# DXP.net
KiCad netlist of a schematic drawn in Altium Designer
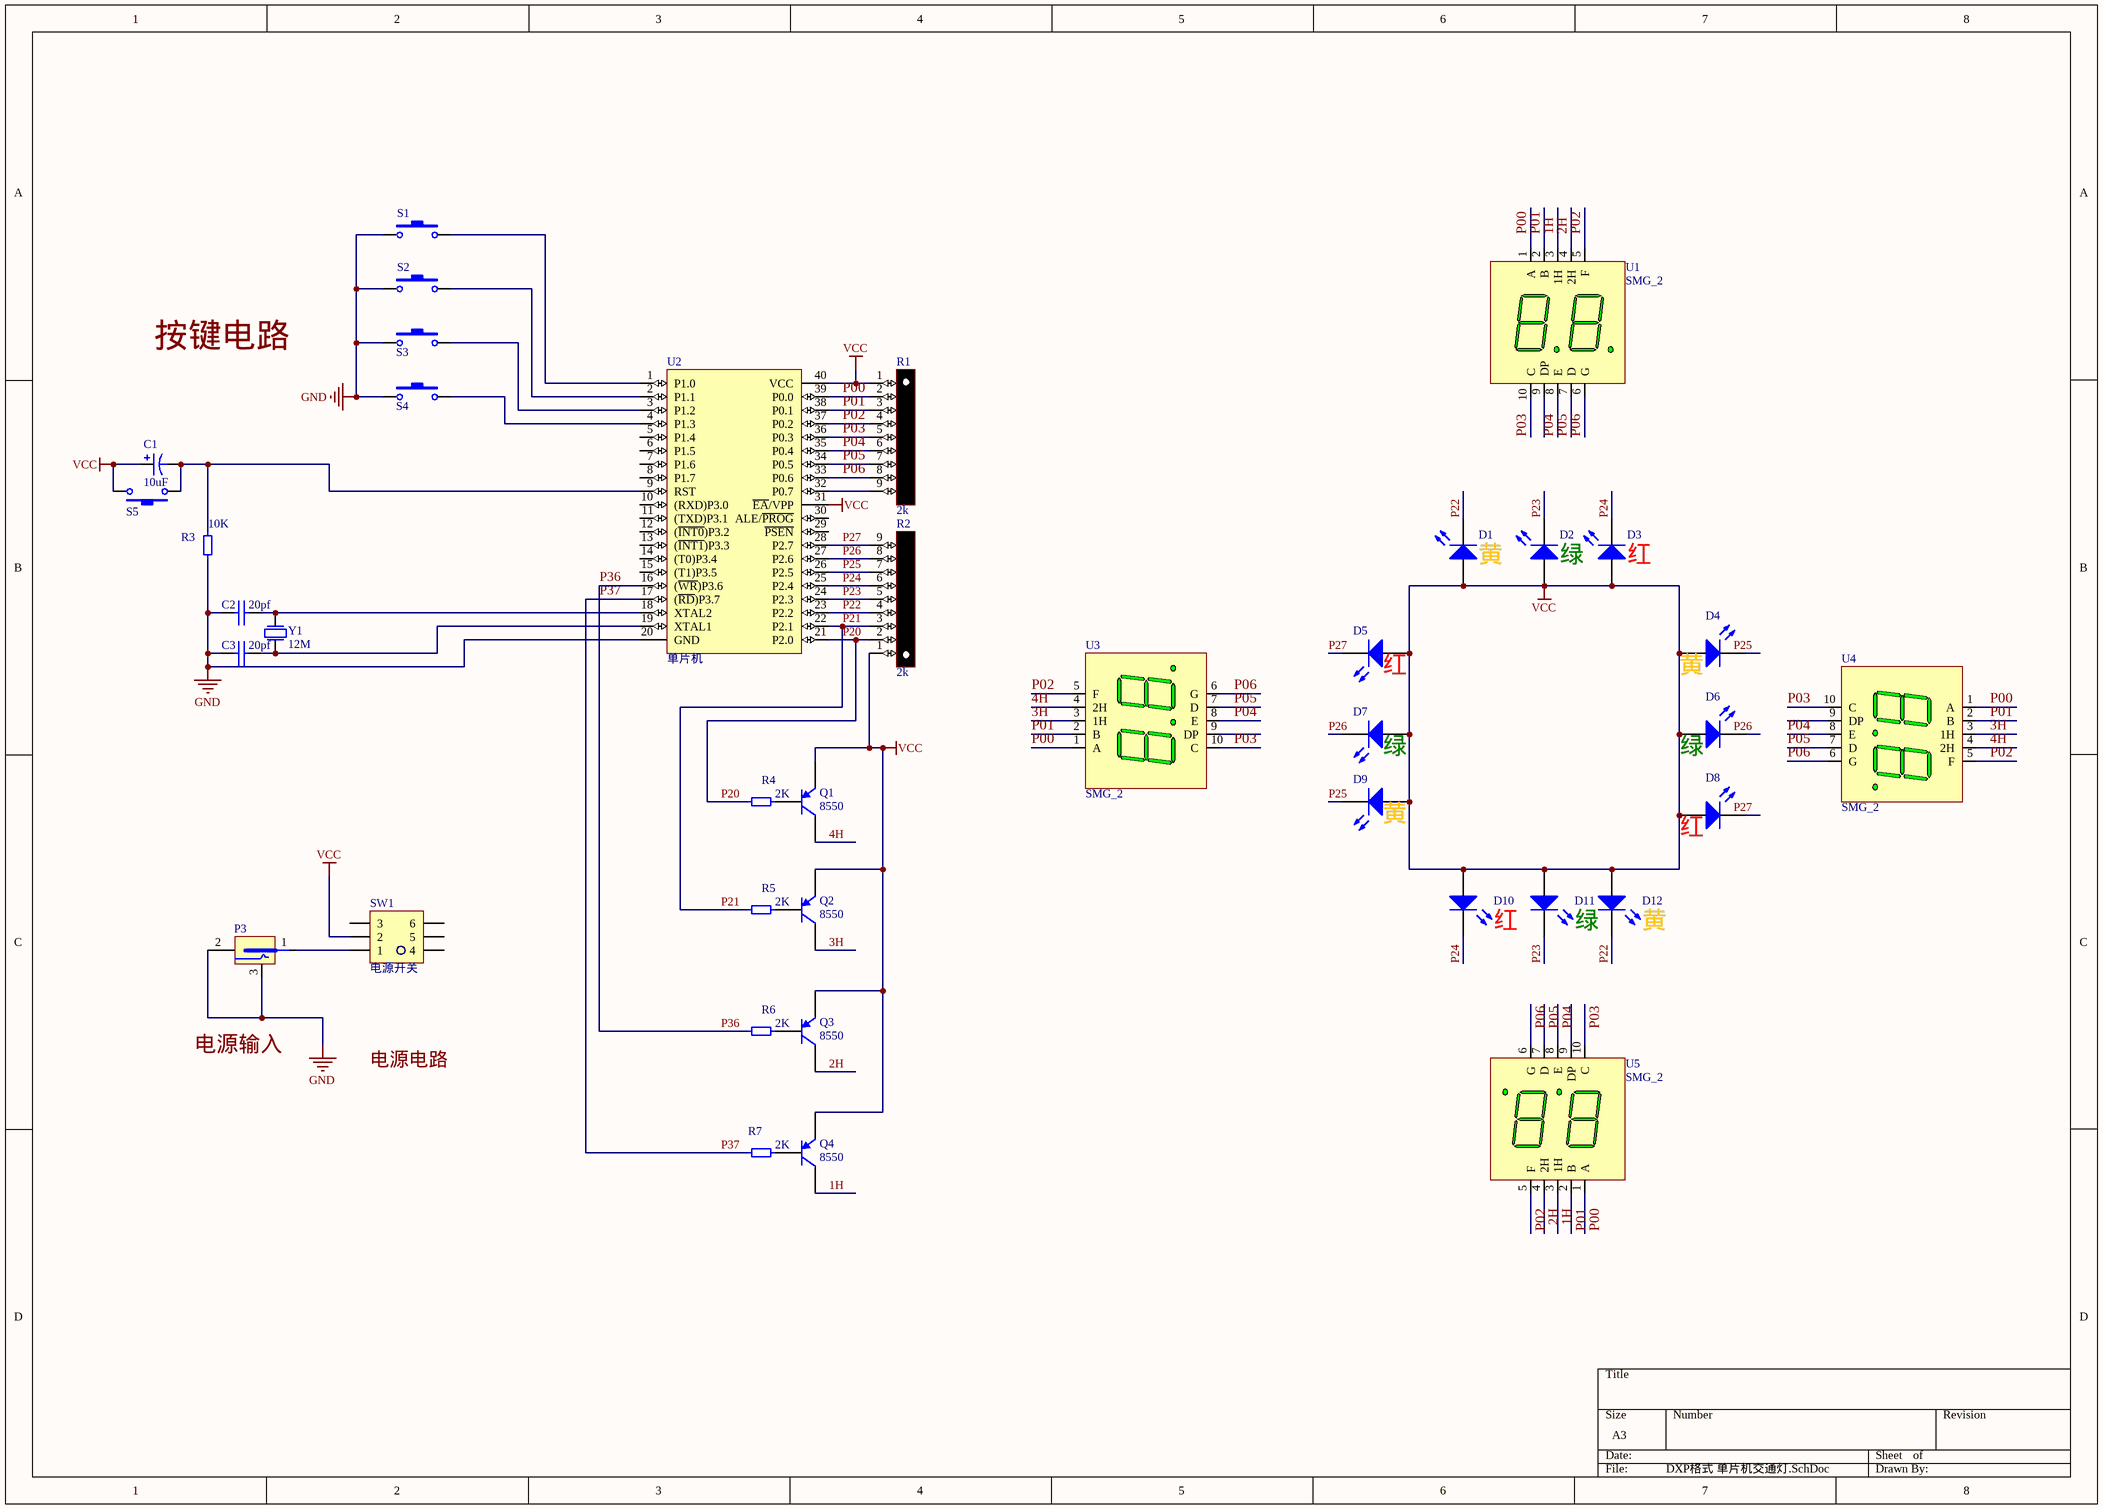
[diagram p0: DXP格式 单片机交通灯.SchDoc]

(export (version "E")
  (design (tool "Eeschema 10.0.6"))
  (components
    (comp (ref "C1")
      (value "10uF")
      (footprint "C_10")
      (description "Polarized Capacitor (Radial)")
      (fields (field (name "PUBLISHER") "Altium Limited"))
      (libsource (lib "简易动环监控系统") (part "Cap Pol1"))
    )
    (comp (ref "C2")
      (value "20pf")
      (footprint "CAP CP")
      (description "电容")
      (libsource (lib "C8051F020最小2") (part "CAP"))
    )
    (comp (ref "C3")
      (value "20pf")
      (footprint "CAP CP")
      (description "电容")
      (libsource (lib "C8051F020最小2") (part "CAP"))
    )
    (comp (ref "D1") (value "黄") (footprint "LED2J") (description "发光二极管") (libsource (lib "亮") (part "LED")))
    (comp (ref "D2") (value "绿") (footprint "LED2J") (description "发光二极管") (libsource (lib "亮") (part "LED")))
    (comp (ref "D3") (value "红") (footprint "LED2J") (description "发光二极管") (libsource (lib "亮") (part "LED")))
    (comp (ref "D4") (value "黄") (footprint "LED2J") (description "发光二极管") (libsource (lib "亮") (part "LED")))
    (comp (ref "D5") (value "红") (footprint "LED2J") (description "发光二极管") (libsource (lib "亮") (part "LED")))
    (comp (ref "D6") (value "绿") (footprint "LED2J") (description "发光二极管") (libsource (lib "亮") (part "LED")))
    (comp (ref "D7") (value "绿") (footprint "LED2J") (description "发光二极管") (libsource (lib "亮") (part "LED")))
    (comp (ref "D8") (value "红") (footprint "LED2J") (description "发光二极管") (libsource (lib "亮") (part "LED")))
    (comp (ref "D9") (value "黄") (footprint "LED2J") (description "发光二极管") (libsource (lib "亮") (part "LED")))
    (comp (ref "D10")
      (value "红")
      (footprint "LED2J")
      (description "发光二极管")
      (libsource (lib "亮") (part "LED"))
    )
    (comp (ref "D11")
      (value "绿")
      (footprint "LED2J")
      (description "发光二极管")
      (libsource (lib "亮") (part "LED"))
    )
    (comp (ref "D12")
      (value "黄")
      (footprint "LED2J")
      (description "发光二极管")
      (libsource (lib "亮") (part "LED"))
    )
    (comp (ref "P3") (value "电源输入") (footprint "DC2.1") (libsource (lib "我自己的") (part "POWER")))
    (comp (ref "Q1")
      (value "8550")
      (footprint "s三极管直插")
      (description "PNP General Purpose Amplifier")
      (fields (field (name "PUBLISHER") "Altium Limited"))
      (libsource (lib "Miscellaneous Devices") (part "2N3906"))
    )
    (comp (ref "Q2")
      (value "8550")
      (footprint "s三极管直插")
      (description "PNP General Purpose Amplifier")
      (fields (field (name "PUBLISHER") "Altium Limited"))
      (libsource (lib "Miscellaneous Devices") (part "2N3906"))
    )
    (comp (ref "Q3")
      (value "8550")
      (footprint "s三极管直插")
      (description "PNP General Purpose Amplifier")
      (fields (field (name "PUBLISHER") "Altium Limited"))
      (libsource (lib "Miscellaneous Devices") (part "2N3906"))
    )
    (comp (ref "Q4")
      (value "8550")
      (footprint "s三极管直插")
      (description "PNP General Purpose Amplifier")
      (fields (field (name "PUBLISHER") "Altium Limited"))
      (libsource (lib "Miscellaneous Devices") (part "2N3906"))
    )
    (comp (ref "R1") (value "2k") (footprint "SIP9") (description "排阻") (libsource (lib "亮") (part "RES9")))
    (comp (ref "R2") (value "2k") (footprint "SIP9") (description "排阻") (libsource (lib "") (part "RES9_1")))
    (comp (ref "R3") (value "10K") (footprint "AXIAL0.3") (libsource (lib "C8051F020最小2") (part "RES2")))
    (comp (ref "R4") (value "2K") (footprint "AXIAL0.3") (libsource (lib "C8051F020最小2") (part "RES2")))
    (comp (ref "R5") (value "2K") (footprint "AXIAL0.3") (libsource (lib "C8051F020最小2") (part "RES2")))
    (comp (ref "R6") (value "2K") (footprint "AXIAL0.3") (libsource (lib "C8051F020最小2") (part "RES2")))
    (comp (ref "R7") (value "2K") (footprint "AXIAL0.3") (libsource (lib "C8051F020最小2") (part "RES2")))
    (comp (ref "S1")
      (value "SW-PB")
      (footprint "key")
      (description "Switch")
      (fields (field (name "PUBLISHER") "Altium Limited"))
      (libsource (lib "实验板原理图") (part "SW-PB"))
    )
    (comp (ref "S2")
      (value "SW-PB")
      (footprint "key")
      (description "Switch")
      (fields (field (name "PUBLISHER") "Altium Limited"))
      (libsource (lib "实验板原理图") (part "SW-PB"))
    )
    (comp (ref "S3")
      (value "SW-PB")
      (footprint "key")
      (description "Switch")
      (fields (field (name "PUBLISHER") "Altium Limited"))
      (libsource (lib "实验板原理图") (part "SW-PB"))
    )
    (comp (ref "S4")
      (value "SW-PB")
      (footprint "key")
      (description "Switch")
      (fields (field (name "PUBLISHER") "Altium Limited"))
      (libsource (lib "实验板原理图") (part "SW-PB"))
    )
    (comp (ref "S5")
      (value "SW-PB")
      (footprint "key")
      (description "Switch")
      (fields (field (name "PUBLISHER") "Altium Limited"))
      (libsource (lib "实验板原理图") (part "SW-PB"))
    )
    (comp (ref "SW1") (value "电源开关") (footprint "sw_自锁 1") (libsource (lib "我自己的") (part "SW1")))
    (comp (ref "U1") (value "SMG_2") (footprint "SMG_2") (libsource (lib "交通灯+上下班高峰调整") (part "SMG_2")))
    (comp (ref "U2") (value "单片机") (footprint "DIP40 - 做板") (libsource (lib "实验板原理图") (part "U1")))
    (comp (ref "U3") (value "SMG_2") (footprint "SMG_2") (libsource (lib "") (part "SMG_2_1")))
    (comp (ref "U4") (value "SMG_2") (footprint "SMG_2") (libsource (lib "") (part "SMG_2_2")))
    (comp (ref "U5") (value "SMG_2") (footprint "SMG_2") (libsource (lib "") (part "SMG_2_3")))
    (comp (ref "Y1")
      (value "12M")
      (footprint "XTAL")
      (description "Crystal Oscillator")
      (libsource (lib "C8051F020最小2") (part "16M"))
    )
  )
  (nets
    (net (code "1") (name "/1H") (class "Default")
      (node (ref "Q4") (pin "3") (pinfunction "C_3") (pintype "passive"))
      (node (ref "U1") (pin "3") (pinfunction "1H_3") (pintype "passive"))
      (node (ref "U5") (pin "3") (pinfunction "1H_3") (pintype "passive"))
    )
    (net (code "2") (name "/2H") (class "Default")
      (node (ref "Q3") (pin "3") (pinfunction "C_3") (pintype "passive"))
      (node (ref "U1") (pin "4") (pinfunction "2H_4") (pintype "passive"))
      (node (ref "U5") (pin "4") (pinfunction "2H_4") (pintype "passive"))
    )
    (net (code "3") (name "/3H") (class "Default")
      (node (ref "Q2") (pin "3") (pinfunction "C_3") (pintype "passive"))
      (node (ref "U3") (pin "3") (pinfunction "1H_3") (pintype "passive"))
      (node (ref "U4") (pin "3") (pinfunction "1H_3") (pintype "passive"))
    )
    (net (code "4") (name "/4H") (class "Default")
      (node (ref "Q1") (pin "3") (pinfunction "C_3") (pintype "passive"))
      (node (ref "U3") (pin "4") (pinfunction "2H_4") (pintype "passive"))
      (node (ref "U4") (pin "4") (pinfunction "2H_4") (pintype "passive"))
    )
    (net (code "5") (name "/P00") (class "Default")
      (node (ref "R1") (pin "2") (pinfunction "2_2") (pintype "bidirectional"))
      (node (ref "U1") (pin "1") (pinfunction "A_1") (pintype "passive"))
      (node (ref "U2") (pin "39") (pinfunction "P0.0_39") (pintype "bidirectional"))
      (node (ref "U3") (pin "1") (pinfunction "A_1") (pintype "passive"))
      (node (ref "U4") (pin "1") (pinfunction "A_1") (pintype "passive"))
      (node (ref "U5") (pin "1") (pinfunction "A_1") (pintype "passive"))
    )
    (net (code "6") (name "/P01") (class "Default")
      (node (ref "R1") (pin "3") (pinfunction "3_3") (pintype "bidirectional"))
      (node (ref "U1") (pin "2") (pinfunction "B_2") (pintype "passive"))
      (node (ref "U2") (pin "38") (pinfunction "P0.1_38") (pintype "bidirectional"))
      (node (ref "U3") (pin "2") (pinfunction "B_2") (pintype "passive"))
      (node (ref "U4") (pin "2") (pinfunction "B_2") (pintype "passive"))
      (node (ref "U5") (pin "2") (pinfunction "B_2") (pintype "passive"))
    )
    (net (code "7") (name "/P02") (class "Default")
      (node (ref "R1") (pin "4") (pinfunction "4_4") (pintype "bidirectional"))
      (node (ref "U1") (pin "5") (pinfunction "F_5") (pintype "passive"))
      (node (ref "U2") (pin "37") (pinfunction "P0.2_37") (pintype "bidirectional"))
      (node (ref "U3") (pin "5") (pinfunction "F_5") (pintype "passive"))
      (node (ref "U4") (pin "5") (pinfunction "F_5") (pintype "passive"))
      (node (ref "U5") (pin "5") (pinfunction "F_5") (pintype "passive"))
    )
    (net (code "8") (name "/P03") (class "Default")
      (node (ref "R1") (pin "5") (pinfunction "5_5") (pintype "bidirectional"))
      (node (ref "U1") (pin "10") (pinfunction "C_10") (pintype "passive"))
      (node (ref "U2") (pin "36") (pinfunction "P0.3_36") (pintype "bidirectional"))
      (node (ref "U3") (pin "10") (pinfunction "C_10") (pintype "passive"))
      (node (ref "U4") (pin "10") (pinfunction "C_10") (pintype "passive"))
      (node (ref "U5") (pin "10") (pinfunction "C_10") (pintype "passive"))
    )
    (net (code "9") (name "/P04") (class "Default")
      (node (ref "R1") (pin "6") (pinfunction "6_6") (pintype "bidirectional"))
      (node (ref "U1") (pin "8") (pinfunction "E_8") (pintype "passive"))
      (node (ref "U2") (pin "35") (pinfunction "P0.4_35") (pintype "bidirectional"))
      (node (ref "U3") (pin "8") (pinfunction "E_8") (pintype "passive"))
      (node (ref "U4") (pin "8") (pinfunction "E_8") (pintype "passive"))
      (node (ref "U5") (pin "8") (pinfunction "E_8") (pintype "passive"))
    )
    (net (code "10") (name "/P05") (class "Default")
      (node (ref "R1") (pin "7") (pinfunction "7_7") (pintype "bidirectional"))
      (node (ref "U1") (pin "7") (pinfunction "D_7") (pintype "passive"))
      (node (ref "U2") (pin "34") (pinfunction "P0.5_34") (pintype "bidirectional"))
      (node (ref "U3") (pin "7") (pinfunction "D_7") (pintype "passive"))
      (node (ref "U4") (pin "7") (pinfunction "D_7") (pintype "passive"))
      (node (ref "U5") (pin "7") (pinfunction "D_7") (pintype "passive"))
    )
    (net (code "11") (name "/P06") (class "Default")
      (node (ref "R1") (pin "8") (pinfunction "8_8") (pintype "bidirectional"))
      (node (ref "U1") (pin "6") (pinfunction "G_6") (pintype "passive"))
      (node (ref "U2") (pin "33") (pinfunction "P0.6_33") (pintype "bidirectional"))
      (node (ref "U3") (pin "6") (pinfunction "G_6") (pintype "passive"))
      (node (ref "U4") (pin "6") (pinfunction "G_6") (pintype "passive"))
      (node (ref "U5") (pin "6") (pinfunction "G_6") (pintype "passive"))
    )
    (net (code "12") (name "/P20") (class "Default")
      (node (ref "R2") (pin "2") (pinfunction "2_2") (pintype "bidirectional"))
      (node (ref "R2") (pin "3") (pinfunction "3_3") (pintype "bidirectional"))
      (node (ref "R4") (pin "2") (pinfunction "2_2") (pintype "passive"))
      (node (ref "R5") (pin "2") (pinfunction "2_2") (pintype "passive"))
      (node (ref "U2") (pin "21") (pinfunction "P2.0_21") (pintype "bidirectional"))
      (node (ref "U2") (pin "22") (pinfunction "P2.1_22") (pintype "bidirectional"))
    )
    (net (code "13") (name "/P22") (class "Default")
      (node (ref "D1") (pin "2") (pinfunction "K_2") (pintype "passive"))
      (node (ref "D12") (pin "2") (pinfunction "K_2") (pintype "passive"))
      (node (ref "R2") (pin "4") (pinfunction "4_4") (pintype "bidirectional"))
      (node (ref "U2") (pin "23") (pinfunction "P2.2_23") (pintype "bidirectional"))
    )
    (net (code "14") (name "/P23") (class "Default")
      (node (ref "D11") (pin "2") (pinfunction "K_2") (pintype "passive"))
      (node (ref "D2") (pin "2") (pinfunction "K_2") (pintype "passive"))
      (node (ref "R2") (pin "5") (pinfunction "5_5") (pintype "bidirectional"))
      (node (ref "U2") (pin "24") (pinfunction "P2.3_24") (pintype "bidirectional"))
    )
    (net (code "15") (name "/P24") (class "Default")
      (node (ref "D10") (pin "2") (pinfunction "K_2") (pintype "passive"))
      (node (ref "D3") (pin "2") (pinfunction "K_2") (pintype "passive"))
      (node (ref "R2") (pin "6") (pinfunction "6_6") (pintype "bidirectional"))
      (node (ref "U2") (pin "25") (pinfunction "P2.4_25") (pintype "bidirectional"))
    )
    (net (code "16") (name "/P25") (class "Default")
      (node (ref "D9") (pin "2") (pinfunction "K_2") (pintype "passive"))
      (node (ref "R2") (pin "7") (pinfunction "7_7") (pintype "bidirectional"))
      (node (ref "U2") (pin "26") (pinfunction "P2.5_26") (pintype "bidirectional"))
    )
    (net (code "17") (name "/P26") (class "Default")
      (node (ref "D7") (pin "2") (pinfunction "K_2") (pintype "passive"))
      (node (ref "R2") (pin "8") (pinfunction "8_8") (pintype "bidirectional"))
      (node (ref "U2") (pin "27") (pinfunction "P2.6_27") (pintype "bidirectional"))
    )
    (net (code "18") (name "/P27") (class "Default")
      (node (ref "D5") (pin "2") (pinfunction "K_2") (pintype "passive"))
      (node (ref "R2") (pin "9") (pinfunction "9_9") (pintype "bidirectional"))
      (node (ref "U2") (pin "28") (pinfunction "P2.7_28") (pintype "bidirectional"))
    )
    (net (code "19") (name "/P36") (class "Default")
      (node (ref "R6") (pin "2") (pinfunction "2_2") (pintype "passive"))
      (node (ref "R7") (pin "2") (pinfunction "2_2") (pintype "passive"))
      (node (ref "U2") (pin "16") (pinfunction "(~{WR})P3.6_16") (pintype "bidirectional"))
      (node (ref "U2") (pin "17") (pinfunction "(~{RD})P3.7_17") (pintype "bidirectional"))
    )
    (net (code "23") (name "GND") (class "Default")
      (node (ref "C2") (pin "1") (pinfunction "1_1") (pintype "passive"))
      (node (ref "C3") (pin "1") (pinfunction "1_1") (pintype "passive"))
      (node (ref "P3") (pin "2") (pintype "passive"))
      (node (ref "P3") (pin "3") (pintype "passive"))
      (node (ref "R3") (pin "1") (pinfunction "1_1") (pintype "passive"))
      (node (ref "S1") (pin "2") (pinfunction "2_2") (pintype "passive"))
      (node (ref "S2") (pin "2") (pinfunction "2_2") (pintype "passive"))
      (node (ref "S3") (pin "2") (pinfunction "2_2") (pintype "passive"))
      (node (ref "S4") (pin "2") (pinfunction "2_2") (pintype "passive"))
      (node (ref "U2") (pin "20") (pinfunction "GND_20") (pintype "power_in"))
    )
    (net (code "24") (name "Net-(P3-Pad1)") (class "Default")
      (node (ref "P3") (pin "1") (pintype "passive"))
      (node (ref "SW1") (pin "1") (pinfunction "1_1") (pintype "passive"))
    )
    (net (code "25") (name "Net-(Q1-B)") (class "Default")
      (node (ref "Q1") (pin "2") (pinfunction "B_2") (pintype "passive"))
      (node (ref "R4") (pin "1") (pinfunction "1_1") (pintype "passive"))
    )
    (net (code "26") (name "Net-(Q2-B)") (class "Default")
      (node (ref "Q2") (pin "2") (pinfunction "B_2") (pintype "passive"))
      (node (ref "R5") (pin "1") (pinfunction "1_1") (pintype "passive"))
    )
    (net (code "27") (name "Net-(Q3-B)") (class "Default")
      (node (ref "Q3") (pin "2") (pinfunction "B_2") (pintype "passive"))
      (node (ref "R6") (pin "1") (pinfunction "1_1") (pintype "passive"))
    )
    (net (code "28") (name "Net-(Q4-B)") (class "Default")
      (node (ref "Q4") (pin "2") (pinfunction "B_2") (pintype "passive"))
      (node (ref "R7") (pin "1") (pinfunction "1_1") (pintype "passive"))
    )
    (net (code "29") (name "Net-(U2-P0.7)") (class "Default")
      (node (ref "R1") (pin "9") (pinfunction "9_9") (pintype "bidirectional"))
      (node (ref "U2") (pin "32") (pinfunction "P0.7_32") (pintype "bidirectional"))
    )
    (net (code "30") (name "Net-(U2-P1.0)") (class "Default")
      (node (ref "S1") (pin "1") (pinfunction "1_1") (pintype "passive"))
      (node (ref "U2") (pin "1") (pinfunction "P1.0_1") (pintype "bidirectional"))
    )
    (net (code "31") (name "Net-(U2-P1.1)") (class "Default")
      (node (ref "S2") (pin "1") (pinfunction "1_1") (pintype "passive"))
      (node (ref "U2") (pin "2") (pinfunction "P1.1_2") (pintype "bidirectional"))
    )
    (net (code "32") (name "Net-(U2-P1.2)") (class "Default")
      (node (ref "S3") (pin "1") (pinfunction "1_1") (pintype "passive"))
      (node (ref "U2") (pin "3") (pinfunction "P1.2_3") (pintype "bidirectional"))
    )
    (net (code "33") (name "Net-(U2-P1.3)") (class "Default")
      (node (ref "S4") (pin "1") (pinfunction "1_1") (pintype "passive"))
      (node (ref "U2") (pin "4") (pinfunction "P1.3_4") (pintype "bidirectional"))
    )
    (net (code "34") (name "Net-(U2-RST)") (class "Default")
      (node (ref "C1") (pin "2") (pinfunction "2_2") (pintype "passive"))
      (node (ref "R3") (pin "2") (pinfunction "2_2") (pintype "passive"))
      (node (ref "S5") (pin "1") (pinfunction "1_1") (pintype "passive"))
      (node (ref "U2") (pin "9") (pinfunction "RST_9") (pintype "bidirectional"))
    )
    (net (code "35") (name "Net-(U2-XTAL1)") (class "Default")
      (node (ref "C3") (pin "2") (pinfunction "2_2") (pintype "passive"))
      (node (ref "U2") (pin "19") (pinfunction "XTAL1_19") (pintype "bidirectional"))
      (node (ref "Y1") (pin "2") (pinfunction "P2_2") (pintype "passive"))
    )
    (net (code "36") (name "Net-(U2-XTAL2)") (class "Default")
      (node (ref "C2") (pin "2") (pinfunction "2_2") (pintype "passive"))
      (node (ref "U2") (pin "18") (pinfunction "XTAL2_18") (pintype "bidirectional"))
      (node (ref "Y1") (pin "1") (pinfunction "P1_1") (pintype "passive"))
    )
    (net (code "37") (name "VCC") (class "Default")
      (node (ref "C1") (pin "1") (pinfunction "1_1") (pintype "passive"))
      (node (ref "D1") (pin "1") (pinfunction "A_1") (pintype "passive"))
      (node (ref "D10") (pin "1") (pinfunction "A_1") (pintype "passive"))
      (node (ref "D11") (pin "1") (pinfunction "A_1") (pintype "passive"))
      (node (ref "D12") (pin "1") (pinfunction "A_1") (pintype "passive"))
      (node (ref "D2") (pin "1") (pinfunction "A_1") (pintype "passive"))
      (node (ref "D3") (pin "1") (pinfunction "A_1") (pintype "passive"))
      (node (ref "D4") (pin "1") (pinfunction "A_1") (pintype "passive"))
      (node (ref "D5") (pin "1") (pinfunction "A_1") (pintype "passive"))
      (node (ref "D6") (pin "1") (pinfunction "A_1") (pintype "passive"))
      (node (ref "D7") (pin "1") (pinfunction "A_1") (pintype "passive"))
      (node (ref "D8") (pin "1") (pinfunction "A_1") (pintype "passive"))
      (node (ref "D9") (pin "1") (pinfunction "A_1") (pintype "passive"))
      (node (ref "Q1") (pin "1") (pinfunction "E_1") (pintype "passive"))
      (node (ref "Q2") (pin "1") (pinfunction "E_1") (pintype "passive"))
      (node (ref "Q3") (pin "1") (pinfunction "E_1") (pintype "passive"))
      (node (ref "Q4") (pin "1") (pinfunction "E_1") (pintype "passive"))
      (node (ref "R1") (pin "1") (pinfunction "COM_1") (pintype "bidirectional"))
      (node (ref "R2") (pin "1") (pinfunction "COM_1") (pintype "bidirectional"))
      (node (ref "S5") (pin "2") (pinfunction "2_2") (pintype "passive"))
      (node (ref "SW1") (pin "2") (pinfunction "2_2") (pintype "passive"))
      (node (ref "U2") (pin "31") (pinfunction "~{EA}/VPP_31") (pintype "power_in"))
      (node (ref "U2") (pin "40") (pinfunction "VCC_40") (pintype "power_in"))
    )
    (net (code "38") (name "unconnected-(D4-K-Pad2)") (class "Default")
      (node (ref "D4") (pin "2") (pinfunction "K_2") (pintype "passive"))
    )
    (net (code "39") (name "unconnected-(D6-K-Pad2)") (class "Default")
      (node (ref "D6") (pin "2") (pinfunction "K_2") (pintype "passive"))
    )
    (net (code "40") (name "unconnected-(D8-K-Pad2)") (class "Default")
      (node (ref "D8") (pin "2") (pinfunction "K_2") (pintype "passive"))
    )
    (net (code "41") (name "unconnected-(SW1-Pad3)") (class "Default")
      (node (ref "SW1") (pin "3") (pinfunction "3_3") (pintype "passive"))
    )
    (net (code "42") (name "unconnected-(SW1-Pad4)") (class "Default")
      (node (ref "SW1") (pin "4") (pinfunction "4_4") (pintype "passive"))
    )
    (net (code "43") (name "unconnected-(SW1-Pad5)") (class "Default")
      (node (ref "SW1") (pin "5") (pinfunction "5_5") (pintype "passive"))
    )
    (net (code "44") (name "unconnected-(SW1-Pad6)") (class "Default")
      (node (ref "SW1") (pin "6") (pinfunction "6_6") (pintype "passive"))
    )
    (net (code "45") (name "unconnected-(U1-DP-Pad9)") (class "Default")
      (node (ref "U1") (pin "9") (pinfunction "DP_9") (pintype "passive"))
    )
    (net (code "46") (name "unconnected-(U2-(RXD)P3.0-Pad10)") (class "Default")
      (node (ref "U2") (pin "10") (pinfunction "(RXD)P3.0_10") (pintype "bidirectional"))
    )
    (net (code "47") (name "unconnected-(U2-(T0)P3.4-Pad14)") (class "Default")
      (node (ref "U2") (pin "14") (pinfunction "(T0)P3.4_14") (pintype "bidirectional"))
    )
    (net (code "48") (name "unconnected-(U2-(T1)P3.5-Pad15)") (class "Default")
      (node (ref "U2") (pin "15") (pinfunction "(T1)P3.5_15") (pintype "bidirectional"))
    )
    (net (code "49") (name "unconnected-(U2-(TXD)P3.1-Pad11)") (class "Default")
      (node (ref "U2") (pin "11") (pinfunction "(TXD)P3.1_11") (pintype "bidirectional"))
    )
    (net (code "50") (name "unconnected-(U2-(~{INT0})P3.2-Pad12)") (class "Default")
      (node (ref "U2") (pin "12") (pinfunction "(~{INT0})P3.2_12") (pintype "bidirectional"))
    )
    (net (code "51") (name "unconnected-(U2-(~{INT1})P3.3-Pad13)") (class "Default")
      (node (ref "U2") (pin "13") (pinfunction "(~{INT1})P3.3_13") (pintype "bidirectional"))
    )
    (net (code "52") (name "unconnected-(U2-ALE{slash}~{PROG}-Pad30)") (class "Default")
      (node (ref "U2") (pin "30") (pinfunction "ALE/~{PROG}_30") (pintype "bidirectional"))
    )
    (net (code "53") (name "unconnected-(U2-P1.4-Pad5)") (class "Default")
      (node (ref "U2") (pin "5") (pinfunction "P1.4_5") (pintype "bidirectional"))
    )
    (net (code "54") (name "unconnected-(U2-P1.5-Pad6)") (class "Default")
      (node (ref "U2") (pin "6") (pinfunction "P1.5_6") (pintype "bidirectional"))
    )
    (net (code "55") (name "unconnected-(U2-P1.6-Pad7)") (class "Default")
      (node (ref "U2") (pin "7") (pinfunction "P1.6_7") (pintype "bidirectional"))
    )
    (net (code "56") (name "unconnected-(U2-P1.7-Pad8)") (class "Default")
      (node (ref "U2") (pin "8") (pinfunction "P1.7_8") (pintype "bidirectional"))
    )
    (net (code "57") (name "unconnected-(U2-~{PSEN}-Pad29)") (class "Default")
      (node (ref "U2") (pin "29") (pinfunction "~{PSEN}_29") (pintype "bidirectional"))
    )
    (net (code "58") (name "unconnected-(U3-DP-Pad9)") (class "Default")
      (node (ref "U3") (pin "9") (pinfunction "DP_9") (pintype "passive"))
    )
    (net (code "59") (name "unconnected-(U4-DP-Pad9)") (class "Default")
      (node (ref "U4") (pin "9") (pinfunction "DP_9") (pintype "passive"))
    )
    (net (code "60") (name "unconnected-(U5-DP-Pad9)") (class "Default")
      (node (ref "U5") (pin "9") (pinfunction "DP_9") (pintype "passive"))
    )
  )
)
